# 10_Peripheral.net
KiCad netlist of a schematic drawn in Altium Designer
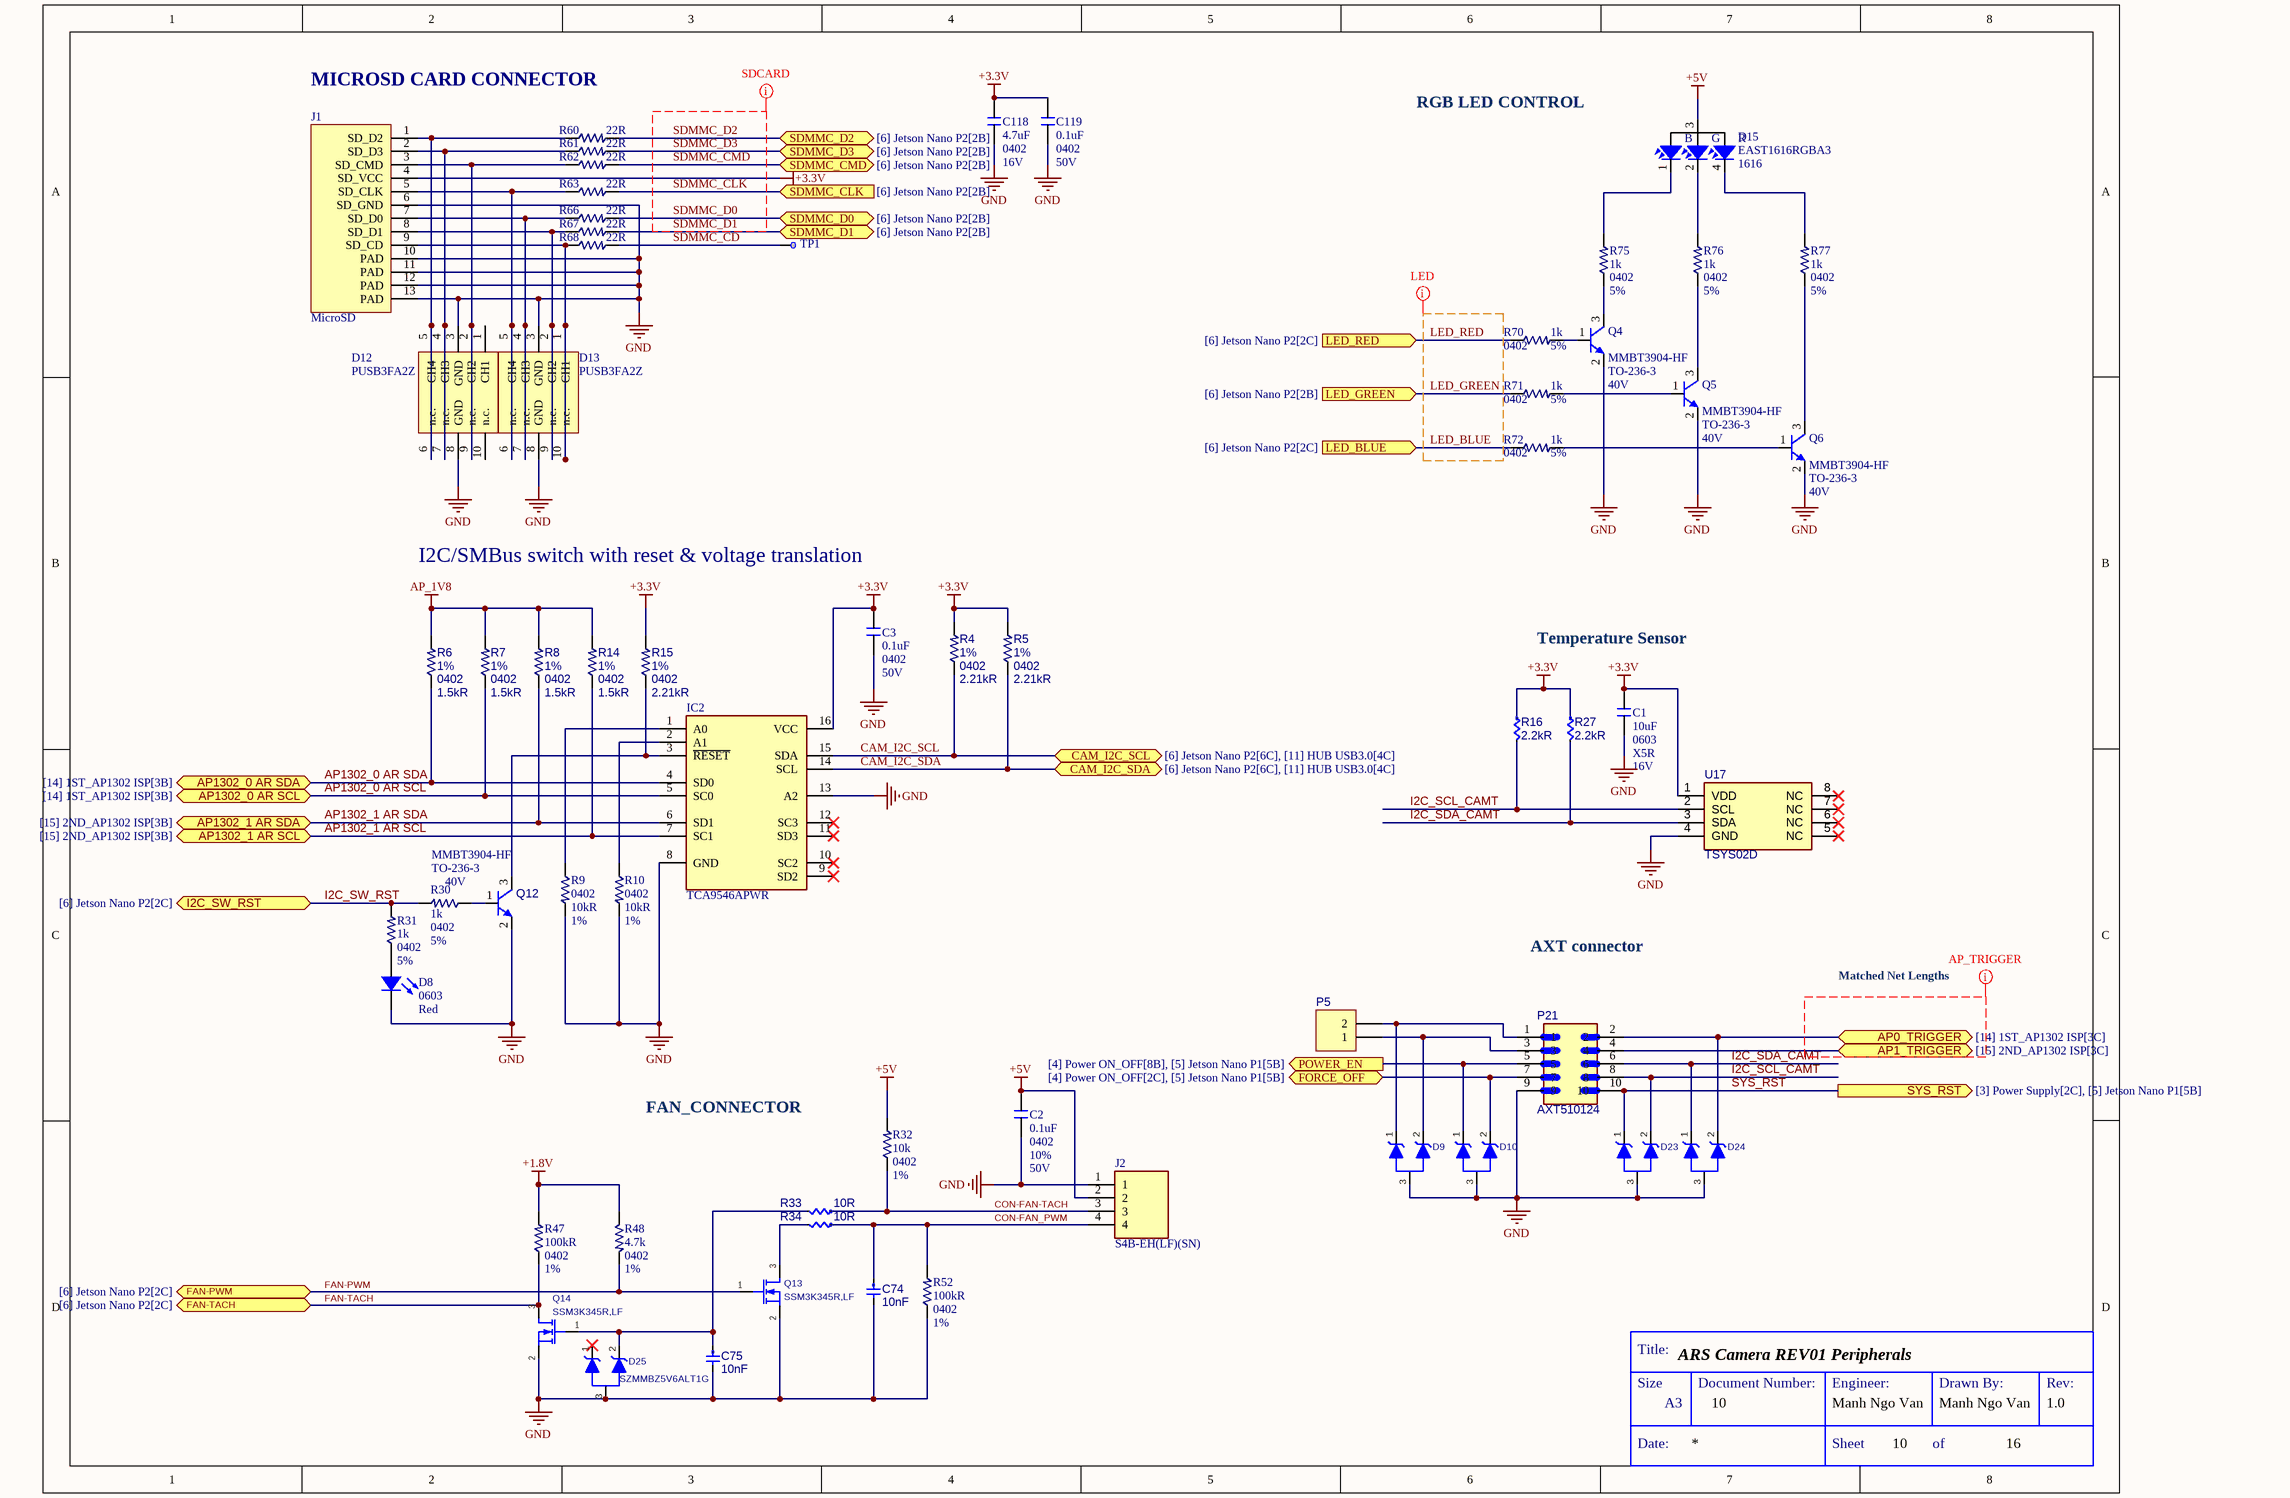
[diagram p0: [10] Peripheral.SchDoc]

(export (version "E")
  (design (tool "Eeschema 10.0.6"))
  (components
    (comp (ref "C1")
      (value "10uF")
      (footprint "C0603M")
      (description "CAP CER 10UF 16V X5R 0603")
      (fields
        (field (name "MANUFACTURER") "Taiyo Yuden")
        (field (name "MANUFACTURER PART NUMBER") "EMK107BBJ106MA-T")
        (field (name "CASE/PACKAGE") "0603")
        (field (name "DIELECTRIC") "X5R")
        (field (name "VOLTAGE RATING (DC)") "16V")
      )
      (libsource (lib "CommonLib") (part "CAP_CER"))
    )
    (comp (ref "C2")
      (value "0.1uF")
      (footprint "C0402M")
      (description "CAP CER 0.1UF 50V X7R 0402")
      (fields
        (field (name "MANUFACTURER") "Murata")
        (field (name "MANUFACTURER PART NUMBER") "GRM155R71H104KE14D")
        (field (name "CASE/PACKAGE") "0402")
        (field (name "TOLERANCE") "10%")
        (field (name "VOLTAGE") "50V")
      )
      (libsource (lib "CommonLib") (part "CAP_CER"))
    )
    (comp (ref "C3")
      (value "0.1uF")
      (footprint "C0402M")
      (description "CAP CER 0.1UF 50V X7R 0402")
      (fields
        (field (name "MANUFACTURER") "Murata")
        (field (name "MANUFACTURER PART NUMBER") "GRM155R71H104KE14D")
        (field (name "CASE/PACKAGE") "0402")
        (field (name "VOLTAGE") "50V")
      )
      (libsource (lib "CommonLib") (part "CAP_CER"))
    )
    (comp (ref "C74")
      (value "885012205050")
      (footprint "CAP0402-M")
      (description "CAP CER 10000PF 25V X7R 0402")
      (fields (field (name "TOLERANCE") "10%") (field (name "CAPACITANCE") "10nF"))
      (libsource (lib "Altium Central") (part "=Capacitance"))
    )
    (comp (ref "C75")
      (value "885012205050")
      (footprint "CAP0402-M")
      (description "CAP CER 10000PF 25V X7R 0402")
      (fields (field (name "TOLERANCE") "10%") (field (name "CAPACITANCE") "10nF"))
      (libsource (lib "Altium Central") (part "=Capacitance"))
    )
    (comp (ref "C118")
      (value "4.7uF")
      (footprint "C0402M")
      (description "CAP CER 4.7UF 16V X5R 0402")
      (fields
        (field (name "MANUFACTURER") "Samsung")
        (field (name "MANUFACTURER PART NUMBER") "CL05A475MO5NUNC")
        (field (name "CASE/PACKAGE") "0402")
        (field (name "VOLTAGE RATING") "16V")
      )
      (libsource (lib "CommonLib") (part "CAP_CER"))
    )
    (comp (ref "C119")
      (value "0.1uF")
      (footprint "C0402M")
      (description "CAP CER 0.1UF 50V X7R 0402")
      (fields
        (field (name "MANUFACTURER") "Murata")
        (field (name "MANUFACTURER PART NUMBER") "GRM155R71H104KE14D")
        (field (name "CASE CODE (IMPERIAL)") "0402")
        (field (name "VOLTAGE") "50V")
      )
      (libsource (lib "CommonLib") (part "CAP_CER"))
    )
    (comp (ref "D8")
      (value "LTST-C190CKT")
      (footprint "LED-0603")
      (description "LED RED CLEAR CHIP SMD")
      (fields (field (name "CASE/PACKAGE") "0603") (field (name "COLOR") "Red"))
      (libsource (lib "CommonLib") (part "Led"))
    )
    (comp (ref "D9")
      (value "SZMMBZ5V6ALT1G")
      (footprint "ONSC-SOT-23-3-318-08_V")
      (description "TVS DIODE 3V 8V SOT23-3")
      (libsource (lib "Altium Central") (part "ONSC-K1K2A3-3"))
    )
    (comp (ref "D10")
      (value "SZMMBZ5V6ALT1G")
      (footprint "ONSC-SOT-23-3-318-08_V")
      (description "TVS DIODE 3V 8V SOT23-3")
      (libsource (lib "Altium Central") (part "ONSC-K1K2A3-3"))
    )
    (comp (ref "D12")
      (value "PUSB3FA2Z")
      (footprint "SON50P100X50-10N")
      (description "ESD Suppressors / TVS Diodes PUSB3FA2 XSON10")
      (libsource (lib "Nauvus") (part "PUSB3FA2Z"))
    )
    (comp (ref "D13")
      (value "PUSB3FA2Z")
      (footprint "SON50P100X50-10N")
      (description "ESD Suppressors / TVS Diodes PUSB3FA2 XSON10")
      (libsource (lib "Nauvus") (part "PUSB3FA2Z"))
    )
    (comp (ref "D15")
      (value "EAST1616RGBA3")
      (footprint "EAST1616RGBA3")
      (description "LED RGB CLEAR 4SMD")
      (fields (field (name "MANUFACTURER") "Everlight") (field (name "CASE CODE (METRIC)") "1616"))
      (libsource (lib "VoiceControl") (part "RGB LED"))
    )
    (comp (ref "D23")
      (value "SZMMBZ5V6ALT1G")
      (footprint "ONSC-SOT-23-3-318-08_V")
      (description "TVS DIODE 3V 8V SOT23-3")
      (libsource (lib "Altium Central") (part "ONSC-K1K2A3-3"))
    )
    (comp (ref "D24")
      (value "SZMMBZ5V6ALT1G")
      (footprint "ONSC-SOT-23-3-318-08_V")
      (description "TVS DIODE 3V 8V SOT23-3")
      (libsource (lib "Altium Central") (part "ONSC-K1K2A3-3"))
    )
    (comp (ref "D25")
      (value "SZMMBZ5V6ALT1G")
      (footprint "ONSC-SOT-23-3-318-08_V")
      (description "TVS DIODE 3V 8V SOT23-3")
      (libsource (lib "Altium Central") (part "ONSC-K1K2A3-3"))
    )
    (comp (ref "IC2")
      (value "TCA9546APWR")
      (footprint "TCA9546APWR")
      (description "4-channel 1.65- to 5.5-V I2C/SMBus switch with reset & voltage translation 16-TSSOP -40 to 85")
      (libsource (lib "Schlib1") (part "TCA9546APWR"))
    )
    (comp (ref "J1")
      (value "MicroSD")
      (footprint "TF_V3")
      (description "MICROSD TF PUSH CONNECTOR")
      (fields (field (name "MANUFACTURER") "SHOU HAN") (field (name "MANUFACTURER PART NUMBER") "TF PUSH"))
      (libsource (lib "Robotic") (part "uSD_TFv3"))
    )
    (comp (ref "J2")
      (value "S4B-EH(LF)(SN)")
      (footprint "S4B-EH(LF)(SN)_1")
      (description "CONN HEADER R/A 4POS 2.5MM")
      (fields (field (name "MANUFACTURER") "JST"))
      (libsource (lib "GPS_DC_DC") (part "S4B-EH_LF__SN_"))
    )
    (comp (ref "P5")
      (value "61300211021")
      (footprint "HDR1X2")
      (description "CONN HEADER R/A 2POS 2.54MM")
      (fields (field (name "MANUFACTURER") "Würth Elektronik GmbH"))
      (libsource (lib "3DAS_4Camera") (part "Header 2"))
    )
    (comp (ref "P21")
      (value "AXT510124")
      (footprint "AXT510124")
      (description "F4S Series 10 Position 0.4 mm Pitch Board to Board SMT Socket Connector")
      (fields (field (name "MANUFACTURER") "Panasonic"))
      (libsource (lib "3DAS_4Camera") (part "AXT510124"))
    )
    (comp (ref "Q4")
      (value "~")
      (footprint "SOT55P160X90-3N")
      (description "TRANS NPN 40V 0.2A SOT523")
      (fields
        (field (name "MANUFACTURER PART NUMBER 1") "MMBT3904-HF")
        (field (name "CASE/PACKAGE") "TO-236-3")
        (field (name "COLLECTOR EMITTER BREAKDOWN VOLTAGE") "40V")
      )
      (libsource (lib "CommonLib") (part "NPN"))
    )
    (comp (ref "Q5")
      (value "~")
      (footprint "SOT55P160X90-3N")
      (description "TRANS NPN 40V 0.2A SOT523")
      (fields
        (field (name "MANUFACTURER PART NUMBER 1") "MMBT3904-HF")
        (field (name "CASE/PACKAGE") "TO-236-3")
        (field (name "COLLECTOR EMITTER BREAKDOWN VOLTAGE") "40V")
      )
      (libsource (lib "CommonLib") (part "NPN"))
    )
    (comp (ref "Q6")
      (value "~")
      (footprint "SOT55P160X90-3N")
      (description "TRANS NPN 40V 0.2A SOT523")
      (fields
        (field (name "MANUFACTURER PART NUMBER 1") "MMBT3904-HF")
        (field (name "CASE/PACKAGE") "TO-236-3")
        (field (name "COLLECTOR EMITTER BREAKDOWN VOLTAGE") "40V")
      )
      (libsource (lib "CommonLib") (part "NPN"))
    )
    (comp (ref "Q12")
      (value "NPN")
      (footprint "SOT55P160X90-3N")
      (description "TRANS NPN 40V 0.2A SOT523")
      (fields
        (field (name "MANUFACTURER PART NUMBER 1") "MMBT3904-HF")
        (field (name "CASE/PACKAGE") "TO-236-3")
        (field (name "COLLECTOR EMITTER BREAKDOWN VOLTAGE") "40V")
      )
      (libsource (lib "3DAS_4Camera") (part "NPN"))
    )
    (comp (ref "Q13")
      (value "SSM3K345R,LF")
      (footprint "SSM3K345R,LF-Footprint-1")
      (description "MOSFET N-CHANNEL 20V 4A SOT23F")
      (libsource (lib "Altium Central") (part "SSM3K345R,LF"))
    )
    (comp (ref "Q14")
      (value "SSM3K345R,LF")
      (footprint "SSM3K345R,LF-Footprint-1")
      (description "MOSFET N-CHANNEL 20V 4A SOT23F")
      (libsource (lib "Altium Central") (part "SSM3K345R,LF"))
    )
    (comp (ref "R4")
      (value "RMCF0402FT2K21")
      (footprint "R0402M")
      (description "RES 2.21K OHM 1% 1/16W 0402")
      (fields
        (field (name "MANUFACTURER") "Stackpole Electronics")
        (field (name "TOLERANCE") "1%")
        (field (name "CASE CODE (IMPERIAL)") "0402")
        (field (name "RESISTANCE") "2.21kR")
      )
      (libsource (lib "3DAS_4Camera") (part "RES_SMD_2.21k"))
    )
    (comp (ref "R5")
      (value "RMCF0402FT2K21")
      (footprint "R0402M")
      (description "RES 2.21K OHM 1% 1/16W 0402")
      (fields
        (field (name "MANUFACTURER") "Stackpole Electronics")
        (field (name "TOLERANCE") "1%")
        (field (name "CASE CODE (IMPERIAL)") "0402")
        (field (name "RESISTANCE") "2.21kR")
      )
      (libsource (lib "3DAS_4Camera") (part "RES_SMD_2.21k"))
    )
    (comp (ref "R6")
      (value "AC0402FR-071K5L")
      (footprint "R0402M")
      (description "RES SMD 1.5K OHM 1% 1/16W 0402")
      (fields
        (field (name "MANUFACTURER") "Yageo")
        (field (name "TOLERANCE") "1%")
        (field (name "CASE/PACKAGE") "0402")
        (field (name "RESISTANCE") "1.5kR")
      )
      (libsource (lib "3DAS_4Camera") (part "RES_SMD_1.5K"))
    )
    (comp (ref "R7")
      (value "AC0402FR-071K5L")
      (footprint "R0402M")
      (description "RES SMD 1.5K OHM 1% 1/16W 0402")
      (fields
        (field (name "MANUFACTURER") "Yageo")
        (field (name "TOLERANCE") "1%")
        (field (name "CASE/PACKAGE") "0402")
        (field (name "RESISTANCE") "1.5kR")
      )
      (libsource (lib "3DAS_4Camera") (part "RES_SMD_1.5K"))
    )
    (comp (ref "R8")
      (value "AC0402FR-071K5L")
      (footprint "R0402M")
      (description "RES SMD 1.5K OHM 1% 1/16W 0402")
      (fields
        (field (name "MANUFACTURER") "Yageo")
        (field (name "TOLERANCE") "1%")
        (field (name "CASE/PACKAGE") "0402")
        (field (name "RESISTANCE") "1.5kR")
      )
      (libsource (lib "3DAS_4Camera") (part "RES_SMD_1.5K"))
    )
    (comp (ref "R9")
      (value "RC0402FR-0710KL")
      (footprint "R0402M")
      (description "RES SMD 10K OHM 1% 1/16W 0402")
      (fields
        (field (name "CASE CODE (IMPERIAL)") "0402")
        (field (name "RESISTANCE") "10kR")
        (field (name "TOLERANCE") "1%")
        (field (name "RESISTANCE TOLERANCE") "1%")
      )
      (libsource (lib "CommonLib") (part "RES_SMD"))
    )
    (comp (ref "R10")
      (value "RC0402FR-0710KL")
      (footprint "R0402M")
      (description "RES SMD 10K OHM 1% 1/16W 0402")
      (fields
        (field (name "CASE CODE (IMPERIAL)") "0402")
        (field (name "RESISTANCE") "10kR")
        (field (name "TOLERANCE") "1%")
        (field (name "RESISTANCE TOLERANCE") "1%")
      )
      (libsource (lib "CommonLib") (part "RES_SMD"))
    )
    (comp (ref "R14")
      (value "AC0402FR-071K5L")
      (footprint "R0402M")
      (description "RES SMD 1.5K OHM 1% 1/16W 0402")
      (fields
        (field (name "MANUFACTURER") "Yageo")
        (field (name "TOLERANCE") "1%")
        (field (name "CASE/PACKAGE") "0402")
        (field (name "RESISTANCE") "1.5kR")
      )
      (libsource (lib "3DAS_4Camera") (part "RES_SMD_1.5K"))
    )
    (comp (ref "R15")
      (value "RMCF0402FT2K21")
      (footprint "R0402M")
      (description "RES 2.21K OHM 1% 1/16W 0402")
      (fields
        (field (name "MANUFACTURER") "Stackpole Electronics")
        (field (name "TOLERANCE") "1%")
        (field (name "CASE CODE (IMPERIAL)") "0402")
        (field (name "RESISTANCE") "2.21kR")
      )
      (libsource (lib "3DAS_4Camera") (part "RES_SMD_2.21k"))
    )
    (comp (ref "R16")
      (value "RC0402FR-072K2L")
      (footprint "RES0402")
      (description "RES SMD 2.2K OHM 1% 1/16W 0402")
      (fields
        (field (name "MANUFACTURER") "Yageo")
        (field (name "RESISTANCE") "2.2kR")
        (field (name "TOLERANCE") "1%")
      )
      (libsource (lib "Altium Central") (part "RES"))
    )
    (comp (ref "R27")
      (value "RC0402FR-072K2L")
      (footprint "RES0402")
      (description "RES SMD 2.2K OHM 1% 1/16W 0402")
      (fields
        (field (name "MANUFACTURER") "Yageo")
        (field (name "RESISTANCE") "2.2kR")
        (field (name "TOLERANCE") "1%")
      )
      (libsource (lib "Altium Central") (part "RES"))
    )
    (comp (ref "R30")
      (value "1k")
      (footprint "R0402M")
      (description "RES SMD 1K OHM 5% 1/16W 0402")
      (fields
        (field (name "MANUFACTURER") "Yageo")
        (field (name "MANUFACTURER PART NUMBER") "RC0402JR-071KL")
        (field (name "CASE CODE (IMPERIAL)") "0402")
        (field (name "TOLERANCE") "5%")
      )
      (libsource (lib "CommonLib") (part "RES_SMD"))
    )
    (comp (ref "R31")
      (value "1k")
      (footprint "R0402M")
      (description "RES SMD 1K OHM 5% 1/16W 0402")
      (fields
        (field (name "MANUFACTURER") "Yageo")
        (field (name "MANUFACTURER PART NUMBER") "RC0402JR-071KL")
        (field (name "CASE CODE (IMPERIAL)") "0402")
        (field (name "TOLERANCE") "5%")
      )
      (libsource (lib "CommonLib") (part "RES_SMD"))
    )
    (comp (ref "R32")
      (value "10k")
      (footprint "R0402M")
      (description "RES SMD 10K OHM 1% 1/16W 0402")
      (fields
        (field (name "MANUFACTURER") "Yageo")
        (field (name "MANUFACTURER PART NUMBER") "RC0402FR-0710KL")
        (field (name "CASE CODE (IMPERIAL)") "0402")
        (field (name "TOLERANCE") "1%")
      )
      (libsource (lib "CommonLib") (part "RES_SMD"))
    )
    (comp (ref "R33")
      (value "RNCP0805FTD10R0")
      (footprint "RES0805")
      (description "RES 10 OHM 1% 1/4W 0805")
      (fields (field (name "TOLERANCE") "1%") (field (name "RESISTANCE") "10R"))
      (libsource (lib "Altium Central") (part "=Resistance"))
    )
    (comp (ref "R34")
      (value "RNCP0805FTD10R0")
      (footprint "RES0805")
      (description "RES 10 OHM 1% 1/4W 0805")
      (fields (field (name "TOLERANCE") "1%") (field (name "RESISTANCE") "10R"))
      (libsource (lib "Altium Central") (part "=Resistance"))
    )
    (comp (ref "R47")
      (value "100kR")
      (footprint "R0402M")
      (description "贴片电阻 100000Ω ± 1.00% 0.0625W ± 100ppm/℃ 0402")
      (fields (field (name "CASE/PACKAGE") "0402") (field (name "TOLERANCE") "1%"))
      (libsource (lib "CommonLib") (part "RES_SMD"))
    )
    (comp (ref "R48")
      (value "4.7k")
      (footprint "R0402M")
      (description "RES SMD 4.7K OHM 1% 1/16W 0402")
      (fields
        (field (name "MANUFACTURER") "Yageo")
        (field (name "MANUFACTURER PART NUMBER") "RC0402FR-074K7L")
        (field (name "CASE CODE (IMPERIAL)") "0402")
        (field (name "TOLERANCE") "1%")
      )
      (libsource (lib "CommonLib") (part "RES_SMD"))
    )
    (comp (ref "R52")
      (value "100kR")
      (footprint "R0402M")
      (description "贴片电阻 100000Ω ± 1.00% 0.0625W ± 100ppm/℃ 0402")
      (fields (field (name "CASE/PACKAGE") "0402") (field (name "TOLERANCE") "1%"))
      (libsource (lib "CommonLib") (part "RES_SMD"))
    )
    (comp (ref "R60")
      (value "22R")
      (footprint "R0402M")
      (description "RES SMD 22R OHM 5% 1/16W 0402")
      (fields
        (field (name "MANUFACTURER") "Yageo")
        (field (name "MANUFACTURER PART NUMBER") "RC0402JR-0722RL")
      )
      (libsource (lib "CommonLib") (part "RES_SMD"))
    )
    (comp (ref "R61")
      (value "22R")
      (footprint "R0402M")
      (description "RES SMD 22R OHM 5% 1/16W 0402")
      (fields
        (field (name "MANUFACTURER") "Yageo")
        (field (name "MANUFACTURER PART NUMBER") "RC0402JR-0722RL")
      )
      (libsource (lib "CommonLib") (part "RES_SMD"))
    )
    (comp (ref "R62")
      (value "22R")
      (footprint "R0402M")
      (description "RES SMD 22R OHM 5% 1/16W 0402")
      (fields
        (field (name "MANUFACTURER") "Yageo")
        (field (name "MANUFACTURER PART NUMBER") "RC0402JR-0722RL")
      )
      (libsource (lib "CommonLib") (part "RES_SMD"))
    )
    (comp (ref "R63")
      (value "22R")
      (footprint "R0402M")
      (description "RES SMD 22R OHM 5% 1/16W 0402")
      (fields
        (field (name "MANUFACTURER") "Yageo")
        (field (name "MANUFACTURER PART NUMBER") "RC0402JR-0722RL")
      )
      (libsource (lib "CommonLib") (part "RES_SMD"))
    )
    (comp (ref "R66")
      (value "22R")
      (footprint "R0402M")
      (description "RES SMD 22R OHM 5% 1/16W 0402")
      (fields
        (field (name "MANUFACTURER") "Yageo")
        (field (name "MANUFACTURER PART NUMBER") "RC0402JR-0722RL")
      )
      (libsource (lib "CommonLib") (part "RES_SMD"))
    )
    (comp (ref "R67")
      (value "22R")
      (footprint "R0402M")
      (description "RES SMD 22R OHM 5% 1/16W 0402")
      (fields
        (field (name "MANUFACTURER") "Yageo")
        (field (name "MANUFACTURER PART NUMBER") "RC0402JR-0722RL")
      )
      (libsource (lib "CommonLib") (part "RES_SMD"))
    )
    (comp (ref "R68")
      (value "22R")
      (footprint "R0402M")
      (description "RES SMD 22R OHM 5% 1/16W 0402")
      (fields
        (field (name "MANUFACTURER") "Yageo")
        (field (name "MANUFACTURER PART NUMBER") "RC0402JR-0722RL")
      )
      (libsource (lib "CommonLib") (part "RES_SMD"))
    )
    (comp (ref "R70")
      (value "1k")
      (footprint "R0402M")
      (description "RES SMD 1K OHM 5% 1/16W 0402")
      (fields
        (field (name "MANUFACTURER") "Yageo")
        (field (name "MANUFACTURER PART NUMBER") "RC0402JR-071KL")
        (field (name "CASE CODE (IMPERIAL)") "0402")
        (field (name "TOLERANCE") "5%")
      )
      (libsource (lib "CommonLib") (part "RES_SMD"))
    )
    (comp (ref "R71")
      (value "1k")
      (footprint "R0402M")
      (description "RES SMD 1K OHM 5% 1/16W 0402")
      (fields
        (field (name "MANUFACTURER") "Yageo")
        (field (name "MANUFACTURER PART NUMBER") "RC0402JR-071KL")
        (field (name "CASE CODE (IMPERIAL)") "0402")
        (field (name "TOLERANCE") "5%")
      )
      (libsource (lib "CommonLib") (part "RES_SMD"))
    )
    (comp (ref "R72")
      (value "1k")
      (footprint "R0402M")
      (description "RES SMD 1K OHM 5% 1/16W 0402")
      (fields
        (field (name "MANUFACTURER") "Yageo")
        (field (name "MANUFACTURER PART NUMBER") "RC0402JR-071KL")
        (field (name "CASE CODE (IMPERIAL)") "0402")
        (field (name "TOLERANCE") "5%")
      )
      (libsource (lib "CommonLib") (part "RES_SMD"))
    )
    (comp (ref "R75")
      (value "1k")
      (footprint "R0402M")
      (description "RES SMD 1K OHM 5% 1/16W 0402")
      (fields
        (field (name "MANUFACTURER") "Yageo")
        (field (name "MANUFACTURER PART NUMBER") "RC0402JR-071KL")
        (field (name "CASE CODE (IMPERIAL)") "0402")
        (field (name "TOLERANCE") "5%")
      )
      (libsource (lib "CommonLib") (part "RES_SMD"))
    )
    (comp (ref "R76")
      (value "1k")
      (footprint "R0402M")
      (description "RES SMD 1K OHM 5% 1/16W 0402")
      (fields
        (field (name "MANUFACTURER") "Yageo")
        (field (name "MANUFACTURER PART NUMBER") "RC0402JR-071KL")
        (field (name "CASE CODE (IMPERIAL)") "0402")
        (field (name "TOLERANCE") "5%")
      )
      (libsource (lib "CommonLib") (part "RES_SMD"))
    )
    (comp (ref "R77")
      (value "1k")
      (footprint "R0402M")
      (description "RES SMD 1K OHM 5% 1/16W 0402")
      (fields
        (field (name "MANUFACTURER") "Yageo")
        (field (name "MANUFACTURER PART NUMBER") "RC0402JR-071KL")
        (field (name "CASE CODE (IMPERIAL)") "0402")
        (field (name "TOLERANCE") "5%")
      )
      (libsource (lib "CommonLib") (part "RES_SMD"))
    )
    (comp (ref "TP1")
      (value "TP")
      (footprint "Test point")
      (description "TESTPOINT")
      (libsource (lib "CommonLib") (part "TestPoint"))
    )
    (comp (ref "U17")
      (value "TSYS02D")
      (footprint "TSYS02D")
      (description "Temperature Sensor, 1DEG C, TDFN-8")
      (fields (field (name "MANUFACTURER") "TE Connectivity"))
      (libsource (lib "3DAS_4Camera") (part "TSYS02D"))
    )
  )
  (nets
    (net (code "1") (name "+1.8V") (class "Default")
      (node (ref "R47") (pin "1") (pinfunction "1_1") (pintype "passive"))
      (node (ref "R48") (pin "2") (pinfunction "2_2") (pintype "passive"))
    )
    (net (code "2") (name "+3.3V") (class "Default")
      (node (ref "C1") (pin "2") (pinfunction "2_2") (pintype "passive"))
      (node (ref "C118") (pin "1") (pinfunction "1_1") (pintype "passive"))
      (node (ref "C119") (pin "2") (pinfunction "2_2") (pintype "passive"))
      (node (ref "C3") (pin "1") (pinfunction "1_1") (pintype "passive"))
      (node (ref "IC2") (pin "16") (pinfunction "VCC_16") (pintype "power_in"))
      (node (ref "J1") (pin "4") (pinfunction "SD_VCC_4") (pintype "passive"))
      (node (ref "R15") (pin "1") (pinfunction "1_1") (pintype "passive"))
      (node (ref "R16") (pin "1") (pinfunction "1_1") (pintype "passive"))
      (node (ref "R27") (pin "1") (pinfunction "1_1") (pintype "passive"))
      (node (ref "R4") (pin "1") (pinfunction "1_1") (pintype "passive"))
      (node (ref "R5") (pin "1") (pinfunction "1_1") (pintype "passive"))
      (node (ref "U17") (pin "1") (pinfunction "VDD_1") (pintype "passive"))
    )
    (net (code "3") (name "+5V") (class "Default")
      (node (ref "C2") (pin "1") (pinfunction "1_1") (pintype "passive"))
      (node (ref "D15") (pin "3") (pinfunction "VDD_3") (pintype "power_in"))
      (node (ref "J2") (pin "2") (pinfunction "2_2") (pintype "passive"))
      (node (ref "R32") (pin "1") (pinfunction "1_1") (pintype "passive"))
    )
    (net (code "4") (name "/AP0_TRIGGER") (class "Default")
      (node (ref "D24") (pin "2") (pinfunction "K2_2") (pintype "passive"))
      (node (ref "P21") (pin "2") (pinfunction "2_2") (pintype "passive"))
    )
    (net (code "5") (name "/AP1_TRIGGER") (class "Default")
      (node (ref "P21") (pin "4") (pinfunction "4_4") (pintype "passive"))
    )
    (net (code "6") (name "/AP1302_0 AR SCL") (class "Default")
      (node (ref "IC2") (pin "5") (pinfunction "SC0_5") (pintype "passive"))
      (node (ref "R7") (pin "2") (pinfunction "2_2") (pintype "passive"))
    )
    (net (code "7") (name "/AP1302_0 AR SDA") (class "Default")
      (node (ref "IC2") (pin "4") (pinfunction "SD0_4") (pintype "passive"))
      (node (ref "R6") (pin "2") (pinfunction "2_2") (pintype "passive"))
    )
    (net (code "8") (name "/AP1302_1 AR SCL") (class "Default")
      (node (ref "IC2") (pin "7") (pinfunction "SC1_7") (pintype "passive"))
      (node (ref "R14") (pin "2") (pinfunction "2_2") (pintype "passive"))
    )
    (net (code "9") (name "/AP1302_1 AR SDA") (class "Default")
      (node (ref "IC2") (pin "6") (pinfunction "SD1_6") (pintype "passive"))
      (node (ref "R8") (pin "2") (pinfunction "2_2") (pintype "passive"))
    )
    (net (code "10") (name "/CAM_I2C_SCL") (class "Default")
      (node (ref "IC2") (pin "15") (pinfunction "SDA_15") (pintype "passive"))
      (node (ref "R4") (pin "2") (pinfunction "2_2") (pintype "passive"))
    )
    (net (code "11") (name "/CAM_I2C_SDA") (class "Default")
      (node (ref "IC2") (pin "14") (pinfunction "SCL_14") (pintype "passive"))
      (node (ref "R5") (pin "2") (pinfunction "2_2") (pintype "passive"))
    )
    (net (code "12") (name "/CON-FAN-TACH") (class "Default")
      (node (ref "J2") (pin "3") (pinfunction "3_3") (pintype "passive"))
      (node (ref "R32") (pin "2") (pinfunction "2_2") (pintype "passive"))
      (node (ref "R33") (pin "1") (pinfunction "1_1") (pintype "passive"))
    )
    (net (code "13") (name "/CON-FAN_PWM") (class "Default")
      (node (ref "C74") (pin "1") (pinfunction "1_1") (pintype "passive"))
      (node (ref "J2") (pin "4") (pinfunction "4_4") (pintype "passive"))
      (node (ref "R34") (pin "1") (pinfunction "1_1") (pintype "passive"))
      (node (ref "R52") (pin "1") (pinfunction "1_1") (pintype "passive"))
    )
    (net (code "14") (name "/FAN-PWM") (class "Default")
      (node (ref "Q13") (pin "1") (pinfunction "G_1") (pintype "passive"))
      (node (ref "R48") (pin "1") (pinfunction "1_1") (pintype "passive"))
    )
    (net (code "15") (name "/FAN-TACH") (class "Default")
      (node (ref "Q14") (pin "3") (pinfunction "D_3") (pintype "passive"))
      (node (ref "R47") (pin "2") (pinfunction "2_2") (pintype "passive"))
    )
    (net (code "16") (name "/FORCE_OFF") (class "Default")
      (node (ref "D10") (pin "2") (pinfunction "K2_2") (pintype "passive"))
      (node (ref "P21") (pin "7") (pinfunction "7_7") (pintype "passive"))
    )
    (net (code "17") (name "/I2C_SCL_CAMT") (class "Default")
      (node (ref "D23") (pin "2") (pinfunction "K2_2") (pintype "passive"))
      (node (ref "P21") (pin "8") (pinfunction "8_8") (pintype "passive"))
      (node (ref "R16") (pin "2") (pinfunction "2_2") (pintype "passive"))
      (node (ref "U17") (pin "2") (pinfunction "SCL_2") (pintype "passive"))
    )
    (net (code "18") (name "/I2C_SDA_CAMT") (class "Default")
      (node (ref "D24") (pin "1") (pinfunction "K1_1") (pintype "passive"))
      (node (ref "P21") (pin "6") (pinfunction "6_6") (pintype "passive"))
      (node (ref "R27") (pin "2") (pinfunction "2_2") (pintype "passive"))
      (node (ref "U17") (pin "3") (pinfunction "SDA_3") (pintype "passive"))
    )
    (net (code "19") (name "/I2C_SW_RST") (class "Default")
      (node (ref "R30") (pin "1") (pinfunction "1_1") (pintype "passive"))
      (node (ref "R31") (pin "1") (pinfunction "1_1") (pintype "passive"))
    )
    (net (code "20") (name "/LED_BLUE") (class "Default")
      (node (ref "R72") (pin "2") (pinfunction "2_2") (pintype "passive"))
    )
    (net (code "21") (name "/LED_GREEN") (class "Default")
      (node (ref "R71") (pin "2") (pinfunction "2_2") (pintype "passive"))
    )
    (net (code "22") (name "/LED_RED") (class "Default")
      (node (ref "R70") (pin "2") (pinfunction "2_2") (pintype "passive"))
    )
    (net (code "23") (name "/POWER_EN") (class "Default")
      (node (ref "D10") (pin "1") (pinfunction "K1_1") (pintype "passive"))
      (node (ref "P21") (pin "5") (pinfunction "5_5") (pintype "passive"))
    )
    (net (code "24") (name "/SDMMC_CD") (class "Default")
      (node (ref "R68") (pin "1") (pinfunction "1_1") (pintype "passive"))
      (node (ref "TP1") (pin "1") (pinfunction "TP_1") (pintype "passive"))
    )
    (net (code "25") (name "/SDMMC_CLK") (class "Default")
      (node (ref "R63") (pin "1") (pinfunction "1_1") (pintype "passive"))
    )
    (net (code "26") (name "/SDMMC_CMD") (class "Default")
      (node (ref "R62") (pin "1") (pinfunction "1_1") (pintype "passive"))
    )
    (net (code "27") (name "/SDMMC_D0") (class "Default")
      (node (ref "R66") (pin "1") (pinfunction "1_1") (pintype "passive"))
    )
    (net (code "28") (name "/SDMMC_D1") (class "Default")
      (node (ref "R67") (pin "1") (pinfunction "1_1") (pintype "passive"))
    )
    (net (code "29") (name "/SDMMC_D2") (class "Default")
      (node (ref "R60") (pin "1") (pinfunction "1_1") (pintype "passive"))
    )
    (net (code "30") (name "/SDMMC_D3") (class "Default")
      (node (ref "R61") (pin "1") (pinfunction "1_1") (pintype "passive"))
    )
    (net (code "31") (name "/SYS_RST") (class "Default")
      (node (ref "D23") (pin "1") (pinfunction "K1_1") (pintype "passive"))
      (node (ref "P21") (pin "10") (pinfunction "10_10") (pintype "passive"))
    )
    (net (code "32") (name "AP_1V8") (class "Default")
      (node (ref "R14") (pin "1") (pinfunction "1_1") (pintype "passive"))
      (node (ref "R6") (pin "1") (pinfunction "1_1") (pintype "passive"))
      (node (ref "R7") (pin "1") (pinfunction "1_1") (pintype "passive"))
      (node (ref "R8") (pin "1") (pinfunction "1_1") (pintype "passive"))
    )
    (net (code "33") (name "GND") (class "Default")
      (node (ref "C1") (pin "1") (pinfunction "1_1") (pintype "passive"))
      (node (ref "C118") (pin "2") (pinfunction "2_2") (pintype "passive"))
      (node (ref "C119") (pin "1") (pinfunction "1_1") (pintype "passive"))
      (node (ref "C2") (pin "2") (pinfunction "2_2") (pintype "passive"))
      (node (ref "C3") (pin "2") (pinfunction "2_2") (pintype "passive"))
      (node (ref "C74") (pin "2") (pinfunction "2_2") (pintype "passive"))
      (node (ref "C75") (pin "2") (pinfunction "2_2") (pintype "passive"))
      (node (ref "D10") (pin "3") (pinfunction "A_3") (pintype "passive"))
      (node (ref "D12") (pin "3") (pinfunction "GND_3") (pintype "passive"))
      (node (ref "D12") (pin "8") (pinfunction "GND_8") (pintype "passive"))
      (node (ref "D13") (pin "3") (pinfunction "GND_3") (pintype "passive"))
      (node (ref "D13") (pin "8") (pinfunction "GND_8") (pintype "passive"))
      (node (ref "D23") (pin "3") (pinfunction "A_3") (pintype "passive"))
      (node (ref "D24") (pin "3") (pinfunction "A_3") (pintype "passive"))
      (node (ref "D25") (pin "3") (pinfunction "A_3") (pintype "passive"))
      (node (ref "D8") (pin "2") (pinfunction "K_2") (pintype "passive"))
      (node (ref "D9") (pin "3") (pinfunction "A_3") (pintype "passive"))
      (node (ref "IC2") (pin "13") (pinfunction "A2_13") (pintype "passive"))
      (node (ref "IC2") (pin "8") (pinfunction "GND_8") (pintype "power_in"))
      (node (ref "J1") (pin "10") (pinfunction "PAD_10") (pintype "passive"))
      (node (ref "J1") (pin "11") (pinfunction "PAD_11") (pintype "passive"))
      (node (ref "J1") (pin "12") (pinfunction "PAD_12") (pintype "passive"))
      (node (ref "J1") (pin "13") (pinfunction "PAD_13") (pintype "passive"))
      (node (ref "J1") (pin "6") (pinfunction "SD_GND_6") (pintype "passive"))
      (node (ref "J2") (pin "1") (pinfunction "1_1") (pintype "passive"))
      (node (ref "P21") (pin "9") (pinfunction "9_9") (pintype "passive"))
      (node (ref "Q12") (pin "2") (pinfunction "E_2") (pintype "passive"))
      (node (ref "Q13") (pin "2") (pinfunction "S_2") (pintype "passive"))
      (node (ref "Q14") (pin "2") (pinfunction "S_2") (pintype "passive"))
      (node (ref "Q4") (pin "2") (pinfunction "E_2") (pintype "passive"))
      (node (ref "Q5") (pin "2") (pinfunction "E_2") (pintype "passive"))
      (node (ref "Q6") (pin "2") (pinfunction "E_2") (pintype "passive"))
      (node (ref "R10") (pin "1") (pinfunction "1_1") (pintype "passive"))
      (node (ref "R52") (pin "2") (pinfunction "2_2") (pintype "passive"))
      (node (ref "R9") (pin "1") (pinfunction "1_1") (pintype "passive"))
      (node (ref "U17") (pin "4") (pinfunction "GND_4") (pintype "passive"))
    )
    (net (code "34") (name "Net-(D8-A)") (class "Default")
      (node (ref "D8") (pin "1") (pinfunction "A_1") (pintype "passive"))
      (node (ref "R31") (pin "2") (pinfunction "2_2") (pintype "passive"))
    )
    (net (code "35") (name "Net-(D9-K1)") (class "Default")
      (node (ref "D9") (pin "1") (pinfunction "K1_1") (pintype "passive"))
      (node (ref "P21") (pin "1") (pinfunction "1_1") (pintype "passive"))
      (node (ref "P5") (pin "2") (pinfunction "2_2") (pintype "passive"))
    )
    (net (code "36") (name "Net-(D9-K2)") (class "Default")
      (node (ref "D9") (pin "2") (pinfunction "K2_2") (pintype "passive"))
      (node (ref "P21") (pin "3") (pinfunction "3_3") (pintype "passive"))
      (node (ref "P5") (pin "1") (pinfunction "1_1") (pintype "passive"))
    )
    (net (code "37") (name "Net-(D12-CH2)") (class "Default")
      (node (ref "D12") (pin "2") (pinfunction "CH2_2") (pintype "passive"))
      (node (ref "D12") (pin "9") (pinfunction "n.c._9") (pintype "passive"))
      (node (ref "J1") (pin "3") (pinfunction "SD_CMD_3") (pintype "passive"))
      (node (ref "R62") (pin "2") (pinfunction "2_2") (pintype "passive"))
    )
    (net (code "38") (name "Net-(D12-CH3)") (class "Default")
      (node (ref "D12") (pin "4") (pinfunction "CH3_4") (pintype "passive"))
      (node (ref "D12") (pin "7") (pinfunction "n.c._7") (pintype "passive"))
      (node (ref "J1") (pin "2") (pinfunction "SD_D3_2") (pintype "passive"))
      (node (ref "R61") (pin "2") (pinfunction "2_2") (pintype "passive"))
    )
    (net (code "39") (name "Net-(D12-CH4)") (class "Default")
      (node (ref "D12") (pin "5") (pinfunction "CH4_5") (pintype "passive"))
      (node (ref "D12") (pin "6") (pinfunction "n.c._6") (pintype "passive"))
      (node (ref "J1") (pin "1") (pinfunction "SD_D2_1") (pintype "passive"))
      (node (ref "R60") (pin "2") (pinfunction "2_2") (pintype "passive"))
    )
    (net (code "40") (name "Net-(D13-CH1)") (class "Default")
      (node (ref "D13") (pin "1") (pinfunction "CH1_1") (pintype "passive"))
      (node (ref "D13") (pin "10") (pinfunction "n.c._10") (pintype "passive"))
      (node (ref "J1") (pin "9") (pinfunction "SD_CD_9") (pintype "passive"))
      (node (ref "R68") (pin "2") (pinfunction "2_2") (pintype "passive"))
    )
    (net (code "41") (name "Net-(D13-CH2)") (class "Default")
      (node (ref "D13") (pin "2") (pinfunction "CH2_2") (pintype "passive"))
      (node (ref "D13") (pin "9") (pinfunction "n.c._9") (pintype "passive"))
      (node (ref "J1") (pin "8") (pinfunction "SD_D1_8") (pintype "passive"))
      (node (ref "R67") (pin "2") (pinfunction "2_2") (pintype "passive"))
    )
    (net (code "42") (name "Net-(D13-CH3)") (class "Default")
      (node (ref "D13") (pin "4") (pinfunction "CH3_4") (pintype "passive"))
      (node (ref "D13") (pin "7") (pinfunction "n.c._7") (pintype "passive"))
      (node (ref "J1") (pin "7") (pinfunction "SD_D0_7") (pintype "passive"))
      (node (ref "R66") (pin "2") (pinfunction "2_2") (pintype "passive"))
    )
    (net (code "43") (name "Net-(D13-CH4)") (class "Default")
      (node (ref "D13") (pin "5") (pinfunction "CH4_5") (pintype "passive"))
      (node (ref "D13") (pin "6") (pinfunction "n.c._6") (pintype "passive"))
      (node (ref "J1") (pin "5") (pinfunction "SD_CLK_5") (pintype "passive"))
      (node (ref "R63") (pin "2") (pinfunction "2_2") (pintype "passive"))
    )
    (net (code "44") (name "Net-(D15-B)") (class "Default")
      (node (ref "D15") (pin "1") (pinfunction "B_1") (pintype "power_in"))
      (node (ref "R75") (pin "1") (pinfunction "1_1") (pintype "passive"))
    )
    (net (code "45") (name "Net-(D15-G)") (class "Default")
      (node (ref "D15") (pin "2") (pinfunction "G_2") (pintype "power_in"))
      (node (ref "R76") (pin "1") (pinfunction "1_1") (pintype "passive"))
    )
    (net (code "46") (name "Net-(D15-R)") (class "Default")
      (node (ref "D15") (pin "4") (pinfunction "R_4") (pintype "power_in"))
      (node (ref "R77") (pin "1") (pinfunction "1_1") (pintype "passive"))
    )
    (net (code "47") (name "Net-(D25-K2)") (class "Default")
      (node (ref "C75") (pin "1") (pinfunction "1_1") (pintype "passive"))
      (node (ref "D25") (pin "2") (pinfunction "K2_2") (pintype "passive"))
      (node (ref "Q14") (pin "1") (pinfunction "G_1") (pintype "passive"))
      (node (ref "R33") (pin "2") (pinfunction "2_2") (pintype "passive"))
    )
    (net (code "48") (name "Net-(IC2-A0)") (class "Default")
      (node (ref "IC2") (pin "1") (pinfunction "A0_1") (pintype "passive"))
      (node (ref "R9") (pin "2") (pinfunction "2_2") (pintype "passive"))
    )
    (net (code "49") (name "Net-(IC2-A1)") (class "Default")
      (node (ref "IC2") (pin "2") (pinfunction "A1_2") (pintype "passive"))
      (node (ref "R10") (pin "2") (pinfunction "2_2") (pintype "passive"))
    )
    (net (code "50") (name "Net-(IC2-~{RESET})") (class "Default")
      (node (ref "IC2") (pin "3") (pinfunction "~{RESET}_3") (pintype "passive"))
      (node (ref "Q12") (pin "3") (pinfunction "C_3") (pintype "passive"))
      (node (ref "R15") (pin "2") (pinfunction "2_2") (pintype "passive"))
    )
    (net (code "51") (name "Net-(Q4-B)") (class "Default")
      (node (ref "Q4") (pin "1") (pinfunction "B_1") (pintype "passive"))
      (node (ref "R70") (pin "1") (pinfunction "1_1") (pintype "passive"))
    )
    (net (code "52") (name "Net-(Q4-C)") (class "Default")
      (node (ref "Q4") (pin "3") (pinfunction "C_3") (pintype "passive"))
      (node (ref "R75") (pin "2") (pinfunction "2_2") (pintype "passive"))
    )
    (net (code "53") (name "Net-(Q5-B)") (class "Default")
      (node (ref "Q5") (pin "1") (pinfunction "B_1") (pintype "passive"))
      (node (ref "R71") (pin "1") (pinfunction "1_1") (pintype "passive"))
    )
    (net (code "54") (name "Net-(Q5-C)") (class "Default")
      (node (ref "Q5") (pin "3") (pinfunction "C_3") (pintype "passive"))
      (node (ref "R76") (pin "2") (pinfunction "2_2") (pintype "passive"))
    )
    (net (code "55") (name "Net-(Q6-B)") (class "Default")
      (node (ref "Q6") (pin "1") (pinfunction "B_1") (pintype "passive"))
      (node (ref "R72") (pin "1") (pinfunction "1_1") (pintype "passive"))
    )
    (net (code "56") (name "Net-(Q6-C)") (class "Default")
      (node (ref "Q6") (pin "3") (pinfunction "C_3") (pintype "passive"))
      (node (ref "R77") (pin "2") (pinfunction "2_2") (pintype "passive"))
    )
    (net (code "57") (name "Net-(Q12-B)") (class "Default")
      (node (ref "Q12") (pin "1") (pinfunction "B_1") (pintype "passive"))
      (node (ref "R30") (pin "2") (pinfunction "2_2") (pintype "passive"))
    )
    (net (code "58") (name "Net-(Q13-D)") (class "Default")
      (node (ref "Q13") (pin "3") (pinfunction "D_3") (pintype "passive"))
      (node (ref "R34") (pin "2") (pinfunction "2_2") (pintype "passive"))
    )
    (net (code "59") (name "unconnected-(D12-CH1-Pad1)") (class "Default")
      (node (ref "D12") (pin "1") (pinfunction "CH1_1") (pintype "passive"))
    )
    (net (code "60") (name "unconnected-(D12-n.c.-Pad10)") (class "Default")
      (node (ref "D12") (pin "10") (pinfunction "n.c._10") (pintype "passive"))
    )
    (net (code "61") (name "unconnected-(D25-K1-Pad1)") (class "Default")
      (node (ref "D25") (pin "1") (pinfunction "K1_1") (pintype "passive+no_connect"))
    )
    (net (code "62") (name "unconnected-(IC2-SC2-Pad10)") (class "Default")
      (node (ref "IC2") (pin "10") (pinfunction "SC2_10") (pintype "passive+no_connect"))
    )
    (net (code "63") (name "unconnected-(IC2-SC3-Pad12)") (class "Default")
      (node (ref "IC2") (pin "12") (pinfunction "SC3_12") (pintype "passive+no_connect"))
    )
    (net (code "64") (name "unconnected-(IC2-SD2-Pad9)") (class "Default")
      (node (ref "IC2") (pin "9") (pinfunction "SD2_9") (pintype "passive+no_connect"))
    )
    (net (code "65") (name "unconnected-(IC2-SD3-Pad11)") (class "Default")
      (node (ref "IC2") (pin "11") (pinfunction "SD3_11") (pintype "passive+no_connect"))
    )
    (net (code "66") (name "unconnected-(U17-NC-Pad5)") (class "Default")
      (node (ref "U17") (pin "5") (pinfunction "NC_5") (pintype "passive+no_connect"))
    )
    (net (code "67") (name "unconnected-(U17-NC-Pad6)") (class "Default")
      (node (ref "U17") (pin "6") (pinfunction "NC_6") (pintype "passive+no_connect"))
    )
    (net (code "68") (name "unconnected-(U17-NC-Pad7)") (class "Default")
      (node (ref "U17") (pin "7") (pinfunction "NC_7") (pintype "passive+no_connect"))
    )
    (net (code "69") (name "unconnected-(U17-NC-Pad8)") (class "Default")
      (node (ref "U17") (pin "8") (pinfunction "NC_8") (pintype "passive+no_connect"))
    )
  )
)
